# tinyha_hat.net
KiCad netlist of a schematic drawn in EAGLE
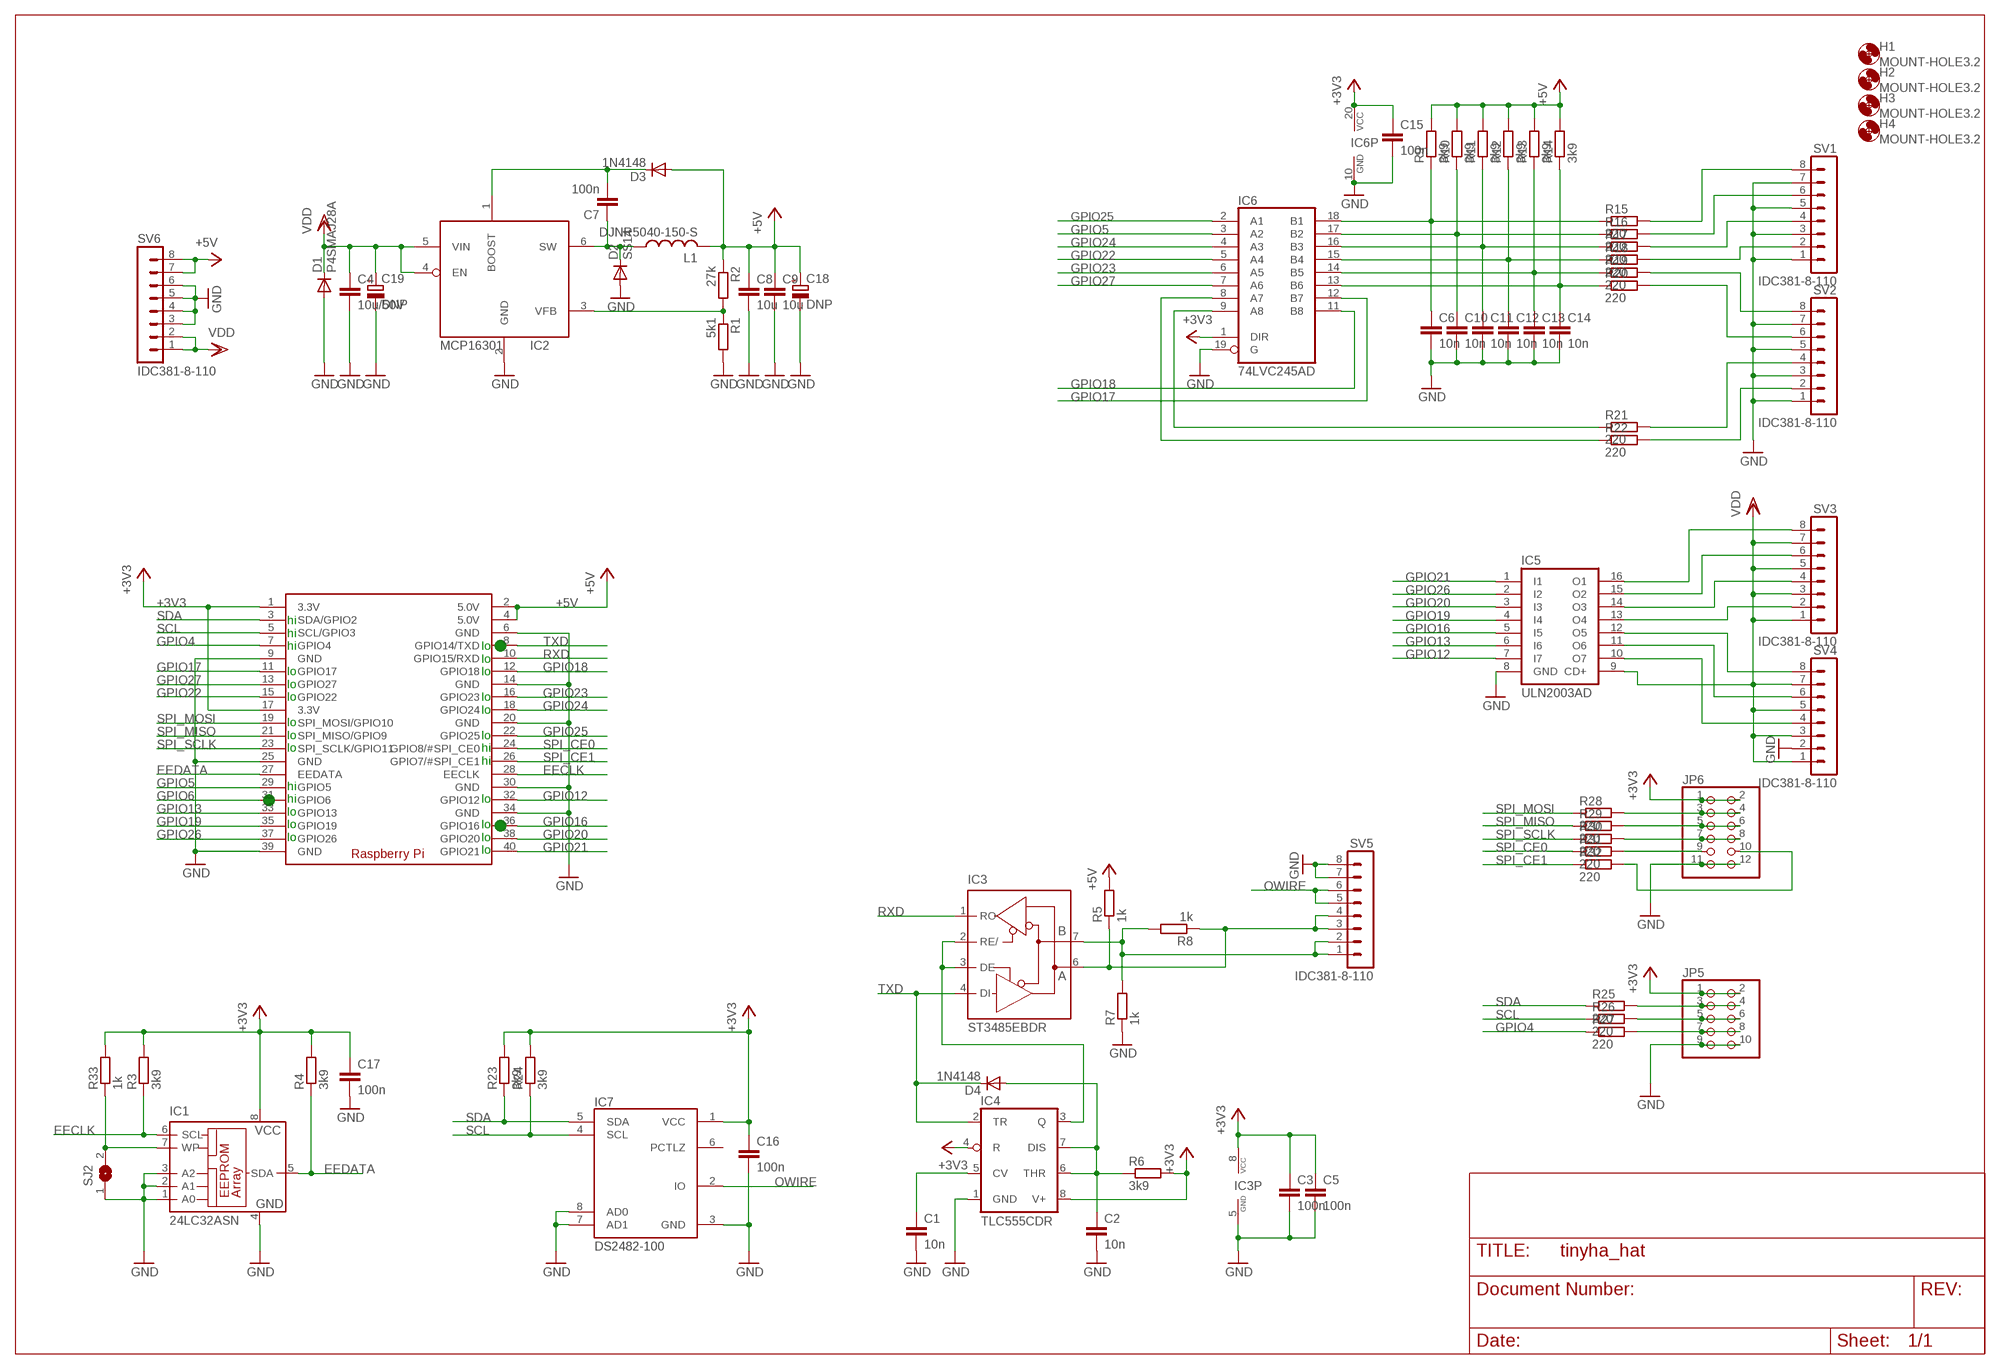
[diagram p0: schematic, sheet 1]

(export (version "E")
  (design (tool "Eeschema 10.0.6"))
  (components
    (comp (ref "C1")
      (value "10n")
      (footprint "eagle-import:C0603K")
      (libsource (lib "eagle-import") (part "C-EUC0603K"))
    )
    (comp (ref "C2")
      (value "10n")
      (footprint "eagle-import:C0603K")
      (libsource (lib "eagle-import") (part "C-EUC0603K"))
    )
    (comp (ref "C3")
      (value "100n")
      (footprint "eagle-import:C0603K")
      (libsource (lib "eagle-import") (part "C-EUC0603K"))
    )
    (comp (ref "C4")
      (value "10u/50V")
      (footprint "eagle-import:C1210K")
      (libsource (lib "eagle-import") (part "C-EUC1210K"))
    )
    (comp (ref "C5")
      (value "100n")
      (footprint "eagle-import:C0603K")
      (libsource (lib "eagle-import") (part "C-EUC0603K"))
    )
    (comp (ref "C6")
      (value "10n")
      (footprint "eagle-import:C0603K")
      (libsource (lib "eagle-import") (part "C-EUC0603K"))
    )
    (comp (ref "C7")
      (value "100n")
      (footprint "eagle-import:C0603K")
      (libsource (lib "eagle-import") (part "C-EUC0603K"))
    )
    (comp (ref "C8")
      (value "10u")
      (footprint "eagle-import:C0805K")
      (libsource (lib "eagle-import") (part "C-EUC0805K"))
    )
    (comp (ref "C9")
      (value "10u")
      (footprint "eagle-import:C0805K")
      (libsource (lib "eagle-import") (part "C-EUC0805K"))
    )
    (comp (ref "C10")
      (value "10n")
      (footprint "eagle-import:C0603K")
      (libsource (lib "eagle-import") (part "C-EUC0603K"))
    )
    (comp (ref "C11")
      (value "10n")
      (footprint "eagle-import:C0603K")
      (libsource (lib "eagle-import") (part "C-EUC0603K"))
    )
    (comp (ref "C12")
      (value "10n")
      (footprint "eagle-import:C0603K")
      (libsource (lib "eagle-import") (part "C-EUC0603K"))
    )
    (comp (ref "C13")
      (value "10n")
      (footprint "eagle-import:C0603K")
      (libsource (lib "eagle-import") (part "C-EUC0603K"))
    )
    (comp (ref "C14")
      (value "10n")
      (footprint "eagle-import:C0603K")
      (libsource (lib "eagle-import") (part "C-EUC0603K"))
    )
    (comp (ref "C15")
      (value "100n")
      (footprint "eagle-import:C0603K")
      (libsource (lib "eagle-import") (part "C-EUC0603K"))
    )
    (comp (ref "C16")
      (value "100n")
      (footprint "eagle-import:C0603K")
      (libsource (lib "eagle-import") (part "C-EUC0603K"))
    )
    (comp (ref "C17")
      (value "100n")
      (footprint "eagle-import:C0603K")
      (libsource (lib "eagle-import") (part "C-EUC0603K"))
    )
    (comp (ref "C18")
      (value "DNP")
      (footprint "eagle-import:E3,5-8")
      (libsource (lib "eagle-import") (part "CPOL-EUE3.5-8"))
    )
    (comp (ref "C19")
      (value "DNP")
      (footprint "eagle-import:E5-10,5")
      (libsource (lib "eagle-import") (part "CPOL-EUE5-10.5"))
    )
    (comp (ref "D1")
      (value "P4SMAJ28A")
      (footprint "eagle-import:DO214AC")
      (libsource (lib "eagle-import") (part "DIODE-DO214AC"))
    )
    (comp (ref "D2")
      (value "SS14")
      (footprint "eagle-import:DO214AC")
      (libsource (lib "eagle-import") (part "DIODE-DO214AC"))
    )
    (comp (ref "D3")
      (value "1N4148")
      (footprint "eagle-import:MICROMELF-W")
      (libsource (lib "eagle-import") (part "DIODE-MICROMELF-W"))
    )
    (comp (ref "D4")
      (value "1N4148")
      (footprint "eagle-import:MICROMELF-W")
      (libsource (lib "eagle-import") (part "DIODE-MICROMELF-W"))
    )
    (comp (ref "H1")
      (value "MOUNT-HOLE3.2")
      (footprint "eagle-import:3,2")
      (libsource (lib "eagle-import") (part "MOUNT-HOLE3.2"))
    )
    (comp (ref "H2")
      (value "MOUNT-HOLE3.2")
      (footprint "eagle-import:3,2")
      (libsource (lib "eagle-import") (part "MOUNT-HOLE3.2"))
    )
    (comp (ref "H3")
      (value "MOUNT-HOLE3.2")
      (footprint "eagle-import:3,2")
      (libsource (lib "eagle-import") (part "MOUNT-HOLE3.2"))
    )
    (comp (ref "H4")
      (value "MOUNT-HOLE3.2")
      (footprint "eagle-import:3,2")
      (libsource (lib "eagle-import") (part "MOUNT-HOLE3.2"))
    )
    (comp (ref "IC1")
      (value "24LC32ASN")
      (footprint "eagle-import:SO-08")
      (fields (field (name "MF") "MICROCHIP") (field (name "MPN") "24LC32A/SN"))
      (libsource (lib "eagle-import") (part "24SNLC32A"))
    )
    (comp (ref "IC2")
      (value "MCP16301")
      (footprint "eagle-import:SOT23-6L")
      (libsource (lib "eagle-import") (part "MCP16301"))
    )
    (comp (ref "IC3")
      (value "ST3485EBDR")
      (footprint "eagle-import:SO08")
      (fields (field (name "MF") "MAXIM") (field (name "MPN") "MAX481CSA"))
      (libsource (lib "eagle-import") (part "MAX481CSA"))
    )
    (comp (ref "IC4")
      (value "TLC555CDR")
      (footprint "eagle-import:SO08")
      (libsource (lib "eagle-import") (part "555DLM"))
    )
    (comp (ref "IC5")
      (value "ULN2003AD")
      (footprint "eagle-import:SO16")
      (libsource (lib "eagle-import") (part "ULN2003AD"))
    )
    (comp (ref "IC6")
      (value "74LVC245AD")
      (footprint "eagle-import:SO20W")
      (libsource (lib "eagle-import") (part "74245DWHC"))
    )
    (comp (ref "IC7")
      (value "DS2482-100")
      (footprint "eagle-import:SOIC-8")
      (libsource (lib "eagle-import") (part "DS2482-100"))
    )
    (comp (ref "JP5")
      (value "PINHD-2X5")
      (footprint "eagle-import:2X05")
      (libsource (lib "eagle-import") (part "PINHD-2X5"))
    )
    (comp (ref "JP6")
      (value "PINHD-2X6")
      (footprint "eagle-import:2X06")
      (libsource (lib "eagle-import") (part "PINHD-2X6"))
    )
    (comp (ref "L1")
      (value "DJNR5040-150-S")
      (footprint "eagle-import:DJNR5040")
      (libsource (lib "eagle-import") (part "DJNR5040"))
    )
    (comp (ref "R1")
      (value "5k1")
      (footprint "eagle-import:R0603")
      (libsource (lib "eagle-import") (part "R-EU_R0603"))
    )
    (comp (ref "R2")
      (value "27k")
      (footprint "eagle-import:R0603")
      (libsource (lib "eagle-import") (part "R-EU_R0603"))
    )
    (comp (ref "R3")
      (value "3k9")
      (footprint "eagle-import:R0603")
      (libsource (lib "eagle-import") (part "R-EU_R0603"))
    )
    (comp (ref "R4")
      (value "3k9")
      (footprint "eagle-import:R0603")
      (libsource (lib "eagle-import") (part "R-EU_R0603"))
    )
    (comp (ref "R5")
      (value "1k")
      (footprint "eagle-import:R0603")
      (libsource (lib "eagle-import") (part "R-EU_R0603"))
    )
    (comp (ref "R6")
      (value "3k9")
      (footprint "eagle-import:R0603")
      (libsource (lib "eagle-import") (part "R-EU_R0603"))
    )
    (comp (ref "R7")
      (value "1k")
      (footprint "eagle-import:R0603")
      (libsource (lib "eagle-import") (part "R-EU_R0603"))
    )
    (comp (ref "R8")
      (value "1k")
      (footprint "eagle-import:R0603")
      (libsource (lib "eagle-import") (part "R-EU_R0603"))
    )
    (comp (ref "R9")
      (value "3k9")
      (footprint "eagle-import:R0603")
      (libsource (lib "eagle-import") (part "R-EU_R0603"))
    )
    (comp (ref "R10")
      (value "3k9")
      (footprint "eagle-import:R0603")
      (libsource (lib "eagle-import") (part "R-EU_R0603"))
    )
    (comp (ref "R11")
      (value "3k9")
      (footprint "eagle-import:R0603")
      (libsource (lib "eagle-import") (part "R-EU_R0603"))
    )
    (comp (ref "R12")
      (value "3k9")
      (footprint "eagle-import:R0603")
      (libsource (lib "eagle-import") (part "R-EU_R0603"))
    )
    (comp (ref "R13")
      (value "3k9")
      (footprint "eagle-import:R0603")
      (libsource (lib "eagle-import") (part "R-EU_R0603"))
    )
    (comp (ref "R14")
      (value "3k9")
      (footprint "eagle-import:R0603")
      (libsource (lib "eagle-import") (part "R-EU_R0603"))
    )
    (comp (ref "R15")
      (value "220")
      (footprint "eagle-import:R0603")
      (libsource (lib "eagle-import") (part "R-EU_R0603"))
    )
    (comp (ref "R16")
      (value "220")
      (footprint "eagle-import:R0603")
      (libsource (lib "eagle-import") (part "R-EU_R0603"))
    )
    (comp (ref "R17")
      (value "220")
      (footprint "eagle-import:R0603")
      (libsource (lib "eagle-import") (part "R-EU_R0603"))
    )
    (comp (ref "R18")
      (value "220")
      (footprint "eagle-import:R0603")
      (libsource (lib "eagle-import") (part "R-EU_R0603"))
    )
    (comp (ref "R19")
      (value "220")
      (footprint "eagle-import:R0603")
      (libsource (lib "eagle-import") (part "R-EU_R0603"))
    )
    (comp (ref "R20")
      (value "220")
      (footprint "eagle-import:R0603")
      (libsource (lib "eagle-import") (part "R-EU_R0603"))
    )
    (comp (ref "R21")
      (value "220")
      (footprint "eagle-import:R0603")
      (libsource (lib "eagle-import") (part "R-EU_R0603"))
    )
    (comp (ref "R22")
      (value "220")
      (footprint "eagle-import:R0603")
      (libsource (lib "eagle-import") (part "R-EU_R0603"))
    )
    (comp (ref "R23")
      (value "3k9")
      (footprint "eagle-import:R0603")
      (libsource (lib "eagle-import") (part "R-EU_R0603"))
    )
    (comp (ref "R24")
      (value "3k9")
      (footprint "eagle-import:R0603")
      (libsource (lib "eagle-import") (part "R-EU_R0603"))
    )
    (comp (ref "R25")
      (value "220")
      (footprint "eagle-import:R0603")
      (libsource (lib "eagle-import") (part "R-EU_R0603"))
    )
    (comp (ref "R26")
      (value "220")
      (footprint "eagle-import:R0603")
      (libsource (lib "eagle-import") (part "R-EU_R0603"))
    )
    (comp (ref "R27")
      (value "220")
      (footprint "eagle-import:R0603")
      (libsource (lib "eagle-import") (part "R-EU_R0603"))
    )
    (comp (ref "R28")
      (value "220")
      (footprint "eagle-import:R0603")
      (libsource (lib "eagle-import") (part "R-EU_R0603"))
    )
    (comp (ref "R29")
      (value "220")
      (footprint "eagle-import:R0603")
      (libsource (lib "eagle-import") (part "R-EU_R0603"))
    )
    (comp (ref "R30")
      (value "220")
      (footprint "eagle-import:R0603")
      (libsource (lib "eagle-import") (part "R-EU_R0603"))
    )
    (comp (ref "R31")
      (value "220")
      (footprint "eagle-import:R0603")
      (libsource (lib "eagle-import") (part "R-EU_R0603"))
    )
    (comp (ref "R32")
      (value "220")
      (footprint "eagle-import:R0603")
      (libsource (lib "eagle-import") (part "R-EU_R0603"))
    )
    (comp (ref "R33")
      (value "1k")
      (footprint "eagle-import:R0603")
      (libsource (lib "eagle-import") (part "R-EU_R0603"))
    )
    (comp (ref "RPI1")
      (value "RASPBERRYPI_BPLUS_ZERO")
      (footprint "eagle-import:PI_HAT_ZERO")
      (libsource (lib "eagle-import") (part "RASPBERRYPI_BPLUS_ZERO"))
    )
    (comp (ref "SJ2") (value "SJ") (footprint "eagle-import:SJ") (libsource (lib "eagle-import") (part "SJ")))
    (comp (ref "SV1")
      (value "IDC381-8-110")
      (footprint "eagle-import:IDC381-8")
      (libsource (lib "eagle-import") (part "MA08-1-IDC"))
    )
    (comp (ref "SV2")
      (value "IDC381-8-110")
      (footprint "eagle-import:IDC381-8")
      (libsource (lib "eagle-import") (part "MA08-1-IDC"))
    )
    (comp (ref "SV3")
      (value "IDC381-8-110")
      (footprint "eagle-import:IDC381-8")
      (libsource (lib "eagle-import") (part "MA08-1-IDC"))
    )
    (comp (ref "SV4")
      (value "IDC381-8-110")
      (footprint "eagle-import:IDC381-8")
      (libsource (lib "eagle-import") (part "MA08-1-IDC"))
    )
    (comp (ref "SV5")
      (value "IDC381-8-110")
      (footprint "eagle-import:IDC381-8")
      (libsource (lib "eagle-import") (part "MA08-1-IDC"))
    )
    (comp (ref "SV6")
      (value "IDC381-8-110")
      (footprint "eagle-import:IDC381-8")
      (libsource (lib "eagle-import") (part "MA08-1-IDC"))
    )
  )
  (nets
    (net (code "1") (name "+3V3") (class "Default")
      (node (ref "C15") (pin "1") (pinfunction "1_1") (pintype "passive"))
      (node (ref "C16") (pin "1") (pinfunction "1_1") (pintype "passive"))
      (node (ref "C17") (pin "1") (pinfunction "1_1") (pintype "passive"))
      (node (ref "C3") (pin "1") (pinfunction "1_1") (pintype "passive"))
      (node (ref "C5") (pin "1") (pinfunction "1_1") (pintype "passive"))
      (node (ref "IC1") (pin "8") (pinfunction "VCC_8") (pintype "power_in"))
      (node (ref "IC3") (pin "8") (pinfunction "VCC_8") (pintype "power_in"))
      (node (ref "IC4") (pin "4") (pinfunction "R_4") (pintype "input"))
      (node (ref "IC4") (pin "8") (pinfunction "V+_8") (pintype "power_in"))
      (node (ref "IC6") (pin "1") (pinfunction "DIR_1") (pintype "input"))
      (node (ref "IC6") (pin "20") (pinfunction "VCC_20") (pintype "power_in"))
      (node (ref "IC7") (pin "1") (pinfunction "VCC_1") (pintype "power_in"))
      (node (ref "JP5") (pin "1") (pinfunction "1_1") (pintype "passive"))
      (node (ref "JP5") (pin "2") (pinfunction "2_2") (pintype "passive"))
      (node (ref "JP6") (pin "1") (pinfunction "1_1") (pintype "passive"))
      (node (ref "JP6") (pin "2") (pinfunction "2_2") (pintype "passive"))
      (node (ref "R23") (pin "2") (pinfunction "2_2") (pintype "passive"))
      (node (ref "R24") (pin "2") (pinfunction "2_2") (pintype "passive"))
      (node (ref "R3") (pin "2") (pinfunction "2_2") (pintype "passive"))
      (node (ref "R33") (pin "2") (pinfunction "2_2") (pintype "passive"))
      (node (ref "R4") (pin "2") (pinfunction "2_2") (pintype "passive"))
      (node (ref "R6") (pin "2") (pinfunction "2_2") (pintype "passive"))
      (node (ref "RPI1") (pin "1") (pinfunction "3.3V_1") (pintype "power_in"))
      (node (ref "RPI1") (pin "17") (pinfunction "3.3V_17") (pintype "power_in"))
    )
    (net (code "2") (name "+5V") (class "Default")
      (node (ref "C18") (pin "+") (pinfunction "+_+") (pintype "passive"))
      (node (ref "C8") (pin "1") (pinfunction "1_1") (pintype "passive"))
      (node (ref "C9") (pin "1") (pinfunction "1_1") (pintype "passive"))
      (node (ref "D3") (pin "A") (pinfunction "A_A") (pintype "passive"))
      (node (ref "L1") (pin "2") (pinfunction "2_2") (pintype "passive"))
      (node (ref "R10") (pin "2") (pinfunction "2_2") (pintype "passive"))
      (node (ref "R11") (pin "2") (pinfunction "2_2") (pintype "passive"))
      (node (ref "R12") (pin "2") (pinfunction "2_2") (pintype "passive"))
      (node (ref "R13") (pin "2") (pinfunction "2_2") (pintype "passive"))
      (node (ref "R14") (pin "2") (pinfunction "2_2") (pintype "passive"))
      (node (ref "R2") (pin "1") (pinfunction "1_1") (pintype "passive"))
      (node (ref "R5") (pin "2") (pinfunction "2_2") (pintype "passive"))
      (node (ref "R9") (pin "2") (pinfunction "2_2") (pintype "passive"))
      (node (ref "RPI1") (pin "2") (pinfunction "5.0V_2") (pintype "power_in"))
      (node (ref "RPI1") (pin "4") (pinfunction "5.0V_4") (pintype "power_in"))
      (node (ref "SV6") (pin "7") (pinfunction "7_7") (pintype "passive"))
      (node (ref "SV6") (pin "8") (pinfunction "8_8") (pintype "passive"))
    )
    (net (code "3") (name "/EECLK") (class "Default")
      (node (ref "IC1") (pin "6") (pinfunction "SCL_6") (pintype "input"))
      (node (ref "R3") (pin "1") (pinfunction "1_1") (pintype "passive"))
      (node (ref "RPI1") (pin "28") (pinfunction "EECLK_28") (pintype "power_in"))
    )
    (net (code "4") (name "/EEDATA") (class "Default")
      (node (ref "IC1") (pin "5") (pinfunction "SDA_5") (pintype "bidirectional"))
      (node (ref "R4") (pin "1") (pinfunction "1_1") (pintype "passive"))
      (node (ref "RPI1") (pin "27") (pinfunction "EEDATA_27") (pintype "bidirectional"))
    )
    (net (code "5") (name "/GPIO4") (class "Default")
      (node (ref "R27") (pin "1") (pinfunction "1_1") (pintype "passive"))
      (node (ref "RPI1") (pin "7") (pinfunction "GPIO4_7") (pintype "bidirectional"))
    )
    (net (code "6") (name "/GPIO5") (class "Default")
      (node (ref "IC6") (pin "3") (pinfunction "A2_3") (pintype "bidirectional"))
      (node (ref "RPI1") (pin "29") (pinfunction "GPIO5_29") (pintype "bidirectional"))
    )
    (net (code "7") (name "/GPIO6") (class "Default")
      (node (ref "RPI1") (pin "31") (pinfunction "GPIO6_31") (pintype "power_in"))
    )
    (net (code "8") (name "/GPIO12") (class "Default")
      (node (ref "IC5") (pin "7") (pinfunction "I7_7") (pintype "input"))
      (node (ref "RPI1") (pin "32") (pinfunction "GPIO12_32") (pintype "bidirectional"))
    )
    (net (code "9") (name "/GPIO13") (class "Default")
      (node (ref "IC5") (pin "6") (pinfunction "I6_6") (pintype "input"))
      (node (ref "RPI1") (pin "33") (pinfunction "GPIO13_33") (pintype "bidirectional"))
    )
    (net (code "10") (name "/GPIO16") (class "Default")
      (node (ref "IC5") (pin "5") (pinfunction "I5_5") (pintype "input"))
      (node (ref "RPI1") (pin "36") (pinfunction "GPIO16_36") (pintype "power_in"))
    )
    (net (code "11") (name "/GPIO17") (class "Default")
      (node (ref "IC6") (pin "12") (pinfunction "B7_12") (pintype "bidirectional"))
      (node (ref "RPI1") (pin "11") (pinfunction "GPIO17_11") (pintype "bidirectional"))
    )
    (net (code "12") (name "/GPIO18") (class "Default")
      (node (ref "IC6") (pin "11") (pinfunction "B8_11") (pintype "bidirectional"))
      (node (ref "RPI1") (pin "12") (pinfunction "GPIO18_12") (pintype "bidirectional"))
    )
    (net (code "13") (name "/GPIO19") (class "Default")
      (node (ref "IC5") (pin "4") (pinfunction "I4_4") (pintype "input"))
      (node (ref "RPI1") (pin "35") (pinfunction "GPIO19_35") (pintype "bidirectional"))
    )
    (net (code "14") (name "/GPIO20") (class "Default")
      (node (ref "IC5") (pin "3") (pinfunction "I3_3") (pintype "input"))
      (node (ref "RPI1") (pin "38") (pinfunction "GPIO20_38") (pintype "bidirectional"))
    )
    (net (code "15") (name "/GPIO21") (class "Default")
      (node (ref "IC5") (pin "1") (pinfunction "I1_1") (pintype "input"))
      (node (ref "RPI1") (pin "40") (pinfunction "GPIO21_40") (pintype "bidirectional"))
    )
    (net (code "16") (name "/GPIO22") (class "Default")
      (node (ref "IC6") (pin "5") (pinfunction "A4_5") (pintype "bidirectional"))
      (node (ref "RPI1") (pin "15") (pinfunction "GPIO22_15") (pintype "bidirectional"))
    )
    (net (code "17") (name "/GPIO23") (class "Default")
      (node (ref "IC6") (pin "6") (pinfunction "A5_6") (pintype "bidirectional"))
      (node (ref "RPI1") (pin "16") (pinfunction "GPIO23_16") (pintype "bidirectional"))
    )
    (net (code "18") (name "/GPIO24") (class "Default")
      (node (ref "IC6") (pin "4") (pinfunction "A3_4") (pintype "bidirectional"))
      (node (ref "RPI1") (pin "18") (pinfunction "GPIO24_18") (pintype "bidirectional"))
    )
    (net (code "19") (name "/GPIO25") (class "Default")
      (node (ref "IC6") (pin "2") (pinfunction "A1_2") (pintype "bidirectional"))
      (node (ref "RPI1") (pin "22") (pinfunction "GPIO25_22") (pintype "bidirectional"))
    )
    (net (code "20") (name "/GPIO26") (class "Default")
      (node (ref "IC5") (pin "2") (pinfunction "I2_2") (pintype "input"))
      (node (ref "RPI1") (pin "37") (pinfunction "GPIO26_37") (pintype "bidirectional"))
    )
    (net (code "21") (name "/GPIO27") (class "Default")
      (node (ref "IC6") (pin "7") (pinfunction "A6_7") (pintype "bidirectional"))
      (node (ref "RPI1") (pin "13") (pinfunction "GPIO27_13") (pintype "bidirectional"))
    )
    (net (code "22") (name "/OWIRE") (class "Default")
      (node (ref "IC7") (pin "2") (pinfunction "IO_2") (pintype "bidirectional"))
      (node (ref "SV5") (pin "5") (pinfunction "5_5") (pintype "passive"))
      (node (ref "SV5") (pin "6") (pinfunction "6_6") (pintype "passive"))
    )
    (net (code "23") (name "/RXD") (class "Default")
      (node (ref "IC3") (pin "1") (pinfunction "RO_1") (pintype "output"))
      (node (ref "RPI1") (pin "10") (pinfunction "GPIO15/RXD_10") (pintype "bidirectional"))
    )
    (net (code "24") (name "/SCL") (class "Default")
      (node (ref "IC7") (pin "4") (pinfunction "SCL_4") (pintype "bidirectional"))
      (node (ref "R24") (pin "1") (pinfunction "1_1") (pintype "passive"))
      (node (ref "R26") (pin "1") (pinfunction "1_1") (pintype "passive"))
      (node (ref "RPI1") (pin "5") (pinfunction "SCL/GPIO3_5") (pintype "bidirectional"))
    )
    (net (code "25") (name "/SDA") (class "Default")
      (node (ref "IC7") (pin "5") (pinfunction "SDA_5") (pintype "bidirectional"))
      (node (ref "R23") (pin "1") (pinfunction "1_1") (pintype "passive"))
      (node (ref "R25") (pin "1") (pinfunction "1_1") (pintype "passive"))
      (node (ref "RPI1") (pin "3") (pinfunction "SDA/GPIO2_3") (pintype "bidirectional"))
    )
    (net (code "26") (name "/SPI_CE0") (class "Default")
      (node (ref "R31") (pin "1") (pinfunction "1_1") (pintype "passive"))
      (node (ref "RPI1") (pin "24") (pinfunction "GPIO8/#SPI_CE0_24") (pintype "bidirectional"))
    )
    (net (code "27") (name "/SPI_CE1") (class "Default")
      (node (ref "R32") (pin "1") (pinfunction "1_1") (pintype "passive"))
      (node (ref "RPI1") (pin "26") (pinfunction "GPIO7/#SPI_CE1_26") (pintype "bidirectional"))
    )
    (net (code "28") (name "/SPI_MISO") (class "Default")
      (node (ref "R29") (pin "1") (pinfunction "1_1") (pintype "passive"))
      (node (ref "RPI1") (pin "21") (pinfunction "SPI_MISO/GPIO9_21") (pintype "bidirectional"))
    )
    (net (code "29") (name "/SPI_MOSI") (class "Default")
      (node (ref "R28") (pin "1") (pinfunction "1_1") (pintype "passive"))
      (node (ref "RPI1") (pin "19") (pinfunction "SPI_MOSI/GPIO10_19") (pintype "bidirectional"))
    )
    (net (code "30") (name "/SPI_SCLK") (class "Default")
      (node (ref "R30") (pin "1") (pinfunction "1_1") (pintype "passive"))
      (node (ref "RPI1") (pin "23") (pinfunction "SPI_SCLK/GPIO11_23") (pintype "bidirectional"))
    )
    (net (code "31") (name "/TXD") (class "Default")
      (node (ref "D4") (pin "C") (pinfunction "C_C") (pintype "passive"))
      (node (ref "IC3") (pin "4") (pinfunction "DI_4") (pintype "input"))
      (node (ref "IC4") (pin "2") (pinfunction "TR_2") (pintype "input"))
      (node (ref "RPI1") (pin "8") (pinfunction "GPIO14/TXD_8") (pintype "output"))
    )
    (net (code "32") (name "GND") (class "Default")
      (node (ref "C1") (pin "2") (pinfunction "2_2") (pintype "passive"))
      (node (ref "C10") (pin "2") (pinfunction "2_2") (pintype "passive"))
      (node (ref "C11") (pin "2") (pinfunction "2_2") (pintype "passive"))
      (node (ref "C12") (pin "2") (pinfunction "2_2") (pintype "passive"))
      (node (ref "C13") (pin "2") (pinfunction "2_2") (pintype "passive"))
      (node (ref "C14") (pin "2") (pinfunction "2_2") (pintype "passive"))
      (node (ref "C15") (pin "2") (pinfunction "2_2") (pintype "passive"))
      (node (ref "C16") (pin "2") (pinfunction "2_2") (pintype "passive"))
      (node (ref "C17") (pin "2") (pinfunction "2_2") (pintype "passive"))
      (node (ref "C18") (pin "-") (pinfunction "-_-") (pintype "passive"))
      (node (ref "C19") (pin "-") (pinfunction "-_-") (pintype "passive"))
      (node (ref "C2") (pin "2") (pinfunction "2_2") (pintype "passive"))
      (node (ref "C3") (pin "2") (pinfunction "2_2") (pintype "passive"))
      (node (ref "C4") (pin "2") (pinfunction "2_2") (pintype "passive"))
      (node (ref "C5") (pin "2") (pinfunction "2_2") (pintype "passive"))
      (node (ref "C6") (pin "2") (pinfunction "2_2") (pintype "passive"))
      (node (ref "C8") (pin "2") (pinfunction "2_2") (pintype "passive"))
      (node (ref "C9") (pin "2") (pinfunction "2_2") (pintype "passive"))
      (node (ref "D1") (pin "A") (pinfunction "A_A") (pintype "passive"))
      (node (ref "D2") (pin "A") (pinfunction "A_A") (pintype "passive"))
      (node (ref "IC1") (pin "1") (pinfunction "A0_1") (pintype "input"))
      (node (ref "IC1") (pin "2") (pinfunction "A1_2") (pintype "input"))
      (node (ref "IC1") (pin "3") (pinfunction "A2_3") (pintype "input"))
      (node (ref "IC1") (pin "4") (pinfunction "GND_4") (pintype "power_in"))
      (node (ref "IC2") (pin "2") (pinfunction "GND_2") (pintype "power_in"))
      (node (ref "IC3") (pin "5") (pinfunction "GND_5") (pintype "power_in"))
      (node (ref "IC4") (pin "1") (pinfunction "GND_1") (pintype "power_in"))
      (node (ref "IC5") (pin "8") (pinfunction "GND_8") (pintype "power_in"))
      (node (ref "IC6") (pin "10") (pinfunction "GND_10") (pintype "power_in"))
      (node (ref "IC6") (pin "19") (pinfunction "G_19") (pintype "input"))
      (node (ref "IC7") (pin "3") (pinfunction "GND_3") (pintype "power_in"))
      (node (ref "IC7") (pin "7") (pinfunction "AD1_7") (pintype "input"))
      (node (ref "IC7") (pin "8") (pinfunction "AD0_8") (pintype "input"))
      (node (ref "JP5") (pin "10") (pinfunction "10_10") (pintype "passive"))
      (node (ref "JP5") (pin "9") (pinfunction "9_9") (pintype "passive"))
      (node (ref "JP6") (pin "11") (pinfunction "11_11") (pintype "passive"))
      (node (ref "JP6") (pin "12") (pinfunction "12_12") (pintype "passive"))
      (node (ref "R1") (pin "2") (pinfunction "2_2") (pintype "passive"))
      (node (ref "R7") (pin "1") (pinfunction "1_1") (pintype "passive"))
      (node (ref "RPI1") (pin "14") (pinfunction "GND_14") (pintype "power_in"))
      (node (ref "RPI1") (pin "20") (pinfunction "GND_20") (pintype "power_in"))
      (node (ref "RPI1") (pin "25") (pinfunction "GND_25") (pintype "power_in"))
      (node (ref "RPI1") (pin "30") (pinfunction "GND_30") (pintype "bidirectional"))
      (node (ref "RPI1") (pin "34") (pinfunction "GND_34") (pintype "bidirectional"))
      (node (ref "RPI1") (pin "39") (pinfunction "GND_39") (pintype "power_in"))
      (node (ref "RPI1") (pin "6") (pinfunction "GND_6") (pintype "power_in"))
      (node (ref "RPI1") (pin "9") (pinfunction "GND_9") (pintype "power_in"))
      (node (ref "SJ2") (pin "1") (pinfunction "1_1") (pintype "passive"))
      (node (ref "SV1") (pin "1") (pinfunction "1_1") (pintype "passive"))
      (node (ref "SV1") (pin "3") (pinfunction "3_3") (pintype "passive"))
      (node (ref "SV1") (pin "5") (pinfunction "5_5") (pintype "passive"))
      (node (ref "SV1") (pin "7") (pinfunction "7_7") (pintype "passive"))
      (node (ref "SV2") (pin "1") (pinfunction "1_1") (pintype "passive"))
      (node (ref "SV2") (pin "3") (pinfunction "3_3") (pintype "passive"))
      (node (ref "SV2") (pin "5") (pinfunction "5_5") (pintype "passive"))
      (node (ref "SV2") (pin "7") (pinfunction "7_7") (pintype "passive"))
      (node (ref "SV4") (pin "2") (pinfunction "2_2") (pintype "passive"))
      (node (ref "SV5") (pin "7") (pinfunction "7_7") (pintype "passive"))
      (node (ref "SV5") (pin "8") (pinfunction "8_8") (pintype "passive"))
      (node (ref "SV6") (pin "3") (pinfunction "3_3") (pintype "passive"))
      (node (ref "SV6") (pin "4") (pinfunction "4_4") (pintype "passive"))
      (node (ref "SV6") (pin "5") (pinfunction "5_5") (pintype "passive"))
      (node (ref "SV6") (pin "6") (pinfunction "6_6") (pintype "passive"))
    )
    (net (code "33") (name "Net-(IC1-WP)") (class "Default")
      (node (ref "IC1") (pin "7") (pinfunction "WP_7") (pintype "input"))
      (node (ref "R33") (pin "1") (pinfunction "1_1") (pintype "passive"))
      (node (ref "SJ2") (pin "2") (pinfunction "2_2") (pintype "passive"))
    )
    (net (code "34") (name "Net-(IC2-BOOST)") (class "Default")
      (node (ref "C7") (pin "2") (pinfunction "2_2") (pintype "passive"))
      (node (ref "D3") (pin "C") (pinfunction "C_C") (pintype "passive"))
      (node (ref "IC2") (pin "1") (pinfunction "BOOST_1") (pintype "passive"))
    )
    (net (code "35") (name "Net-(IC2-SW)") (class "Default")
      (node (ref "C7") (pin "1") (pinfunction "1_1") (pintype "passive"))
      (node (ref "D2") (pin "C") (pinfunction "C_C") (pintype "passive"))
      (node (ref "IC2") (pin "6") (pinfunction "SW_6") (pintype "passive"))
      (node (ref "L1") (pin "1") (pinfunction "1_1") (pintype "passive"))
    )
    (net (code "36") (name "Net-(IC2-VFB)") (class "Default")
      (node (ref "IC2") (pin "3") (pinfunction "VFB_3") (pintype "input"))
      (node (ref "R1") (pin "1") (pinfunction "1_1") (pintype "passive"))
      (node (ref "R2") (pin "2") (pinfunction "2_2") (pintype "passive"))
    )
    (net (code "37") (name "Net-(IC3A-A)") (class "Default")
      (node (ref "IC3") (pin "6") (pinfunction "A_6") (pintype "passive"))
      (node (ref "R5") (pin "1") (pinfunction "1_1") (pintype "passive"))
      (node (ref "R8") (pin "1") (pinfunction "1_1") (pintype "passive"))
      (node (ref "SV5") (pin "3") (pinfunction "3_3") (pintype "passive"))
      (node (ref "SV5") (pin "4") (pinfunction "4_4") (pintype "passive"))
    )
    (net (code "38") (name "Net-(IC3A-B)") (class "Default")
      (node (ref "IC3") (pin "7") (pinfunction "B_7") (pintype "passive"))
      (node (ref "R7") (pin "2") (pinfunction "2_2") (pintype "passive"))
      (node (ref "R8") (pin "2") (pinfunction "2_2") (pintype "passive"))
      (node (ref "SV5") (pin "1") (pinfunction "1_1") (pintype "passive"))
      (node (ref "SV5") (pin "2") (pinfunction "2_2") (pintype "passive"))
    )
    (net (code "39") (name "Net-(IC3A-DE)") (class "Default")
      (node (ref "IC3") (pin "2") (pinfunction "RE/_2") (pintype "input"))
      (node (ref "IC3") (pin "3") (pinfunction "DE_3") (pintype "input"))
      (node (ref "IC4") (pin "3") (pinfunction "Q_3") (pintype "output"))
    )
    (net (code "40") (name "Net-(IC4-CV)") (class "Default")
      (node (ref "C1") (pin "1") (pinfunction "1_1") (pintype "passive"))
      (node (ref "IC4") (pin "5") (pinfunction "CV_5") (pintype "input"))
    )
    (net (code "41") (name "Net-(IC4-DIS)") (class "Default")
      (node (ref "C2") (pin "1") (pinfunction "1_1") (pintype "passive"))
      (node (ref "D4") (pin "A") (pinfunction "A_A") (pintype "passive"))
      (node (ref "IC4") (pin "6") (pinfunction "THR_6") (pintype "input"))
      (node (ref "IC4") (pin "7") (pinfunction "DIS_7") (pintype "input"))
      (node (ref "R6") (pin "1") (pinfunction "1_1") (pintype "passive"))
    )
    (net (code "42") (name "Net-(IC5-O1)") (class "Default")
      (node (ref "IC5") (pin "16") (pinfunction "O1_16") (pintype "open_collector"))
      (node (ref "SV3") (pin "8") (pinfunction "8_8") (pintype "passive"))
    )
    (net (code "43") (name "Net-(IC5-O2)") (class "Default")
      (node (ref "IC5") (pin "15") (pinfunction "O2_15") (pintype "open_collector"))
      (node (ref "SV3") (pin "6") (pinfunction "6_6") (pintype "passive"))
    )
    (net (code "44") (name "Net-(IC5-O3)") (class "Default")
      (node (ref "IC5") (pin "14") (pinfunction "O3_14") (pintype "open_collector"))
      (node (ref "SV3") (pin "4") (pinfunction "4_4") (pintype "passive"))
    )
    (net (code "45") (name "Net-(IC5-O4)") (class "Default")
      (node (ref "IC5") (pin "13") (pinfunction "O4_13") (pintype "open_collector"))
      (node (ref "SV3") (pin "2") (pinfunction "2_2") (pintype "passive"))
    )
    (net (code "46") (name "Net-(IC5-O5)") (class "Default")
      (node (ref "IC5") (pin "12") (pinfunction "O5_12") (pintype "open_collector"))
      (node (ref "SV4") (pin "8") (pinfunction "8_8") (pintype "passive"))
    )
    (net (code "47") (name "Net-(IC5-O6)") (class "Default")
      (node (ref "IC5") (pin "11") (pinfunction "O6_11") (pintype "open_collector"))
      (node (ref "SV4") (pin "6") (pinfunction "6_6") (pintype "passive"))
    )
    (net (code "48") (name "Net-(IC5-O7)") (class "Default")
      (node (ref "IC5") (pin "10") (pinfunction "O7_10") (pintype "open_collector"))
      (node (ref "SV4") (pin "4") (pinfunction "4_4") (pintype "passive"))
    )
    (net (code "49") (name "Net-(IC6A-A7)") (class "Default")
      (node (ref "IC6") (pin "8") (pinfunction "A7_8") (pintype "bidirectional"))
      (node (ref "R22") (pin "1") (pinfunction "1_1") (pintype "passive"))
    )
    (net (code "50") (name "Net-(IC6A-A8)") (class "Default")
      (node (ref "IC6") (pin "9") (pinfunction "A8_9") (pintype "bidirectional"))
      (node (ref "R21") (pin "1") (pinfunction "1_1") (pintype "passive"))
    )
    (net (code "51") (name "Net-(IC6A-B1)") (class "Default")
      (node (ref "C6") (pin "1") (pinfunction "1_1") (pintype "passive"))
      (node (ref "IC6") (pin "18") (pinfunction "B1_18") (pintype "bidirectional"))
      (node (ref "R15") (pin "1") (pinfunction "1_1") (pintype "passive"))
      (node (ref "R9") (pin "1") (pinfunction "1_1") (pintype "passive"))
    )
    (net (code "52") (name "Net-(IC6A-B2)") (class "Default")
      (node (ref "C10") (pin "1") (pinfunction "1_1") (pintype "passive"))
      (node (ref "IC6") (pin "17") (pinfunction "B2_17") (pintype "bidirectional"))
      (node (ref "R10") (pin "1") (pinfunction "1_1") (pintype "passive"))
      (node (ref "R16") (pin "1") (pinfunction "1_1") (pintype "passive"))
    )
    (net (code "53") (name "Net-(IC6A-B3)") (class "Default")
      (node (ref "C11") (pin "1") (pinfunction "1_1") (pintype "passive"))
      (node (ref "IC6") (pin "16") (pinfunction "B3_16") (pintype "bidirectional"))
      (node (ref "R11") (pin "1") (pinfunction "1_1") (pintype "passive"))
      (node (ref "R17") (pin "1") (pinfunction "1_1") (pintype "passive"))
    )
    (net (code "54") (name "Net-(IC6A-B4)") (class "Default")
      (node (ref "C12") (pin "1") (pinfunction "1_1") (pintype "passive"))
      (node (ref "IC6") (pin "15") (pinfunction "B4_15") (pintype "bidirectional"))
      (node (ref "R12") (pin "1") (pinfunction "1_1") (pintype "passive"))
      (node (ref "R18") (pin "1") (pinfunction "1_1") (pintype "passive"))
    )
    (net (code "55") (name "Net-(IC6A-B5)") (class "Default")
      (node (ref "C13") (pin "1") (pinfunction "1_1") (pintype "passive"))
      (node (ref "IC6") (pin "14") (pinfunction "B5_14") (pintype "bidirectional"))
      (node (ref "R13") (pin "1") (pinfunction "1_1") (pintype "passive"))
      (node (ref "R19") (pin "1") (pinfunction "1_1") (pintype "passive"))
    )
    (net (code "56") (name "Net-(IC6A-B6)") (class "Default")
      (node (ref "C14") (pin "1") (pinfunction "1_1") (pintype "passive"))
      (node (ref "IC6") (pin "13") (pinfunction "B6_13") (pintype "bidirectional"))
      (node (ref "R14") (pin "1") (pinfunction "1_1") (pintype "passive"))
      (node (ref "R20") (pin "1") (pinfunction "1_1") (pintype "passive"))
    )
    (net (code "57") (name "Net-(JP5-Pad3)") (class "Default")
      (node (ref "JP5") (pin "3") (pinfunction "3_3") (pintype "passive"))
      (node (ref "JP5") (pin "4") (pinfunction "4_4") (pintype "passive"))
      (node (ref "R25") (pin "2") (pinfunction "2_2") (pintype "passive"))
    )
    (net (code "58") (name "Net-(JP5-Pad5)") (class "Default")
      (node (ref "JP5") (pin "5") (pinfunction "5_5") (pintype "passive"))
      (node (ref "JP5") (pin "6") (pinfunction "6_6") (pintype "passive"))
      (node (ref "R26") (pin "2") (pinfunction "2_2") (pintype "passive"))
    )
    (net (code "59") (name "Net-(JP5-Pad7)") (class "Default")
      (node (ref "JP5") (pin "7") (pinfunction "7_7") (pintype "passive"))
      (node (ref "JP5") (pin "8") (pinfunction "8_8") (pintype "passive"))
      (node (ref "R27") (pin "2") (pinfunction "2_2") (pintype "passive"))
    )
    (net (code "60") (name "Net-(JP6-Pad3)") (class "Default")
      (node (ref "JP6") (pin "3") (pinfunction "3_3") (pintype "passive"))
      (node (ref "JP6") (pin "4") (pinfunction "4_4") (pintype "passive"))
      (node (ref "R28") (pin "2") (pinfunction "2_2") (pintype "passive"))
    )
    (net (code "61") (name "Net-(JP6-Pad5)") (class "Default")
      (node (ref "JP6") (pin "5") (pinfunction "5_5") (pintype "passive"))
      (node (ref "JP6") (pin "6") (pinfunction "6_6") (pintype "passive"))
      (node (ref "R29") (pin "2") (pinfunction "2_2") (pintype "passive"))
    )
    (net (code "62") (name "Net-(JP6-Pad7)") (class "Default")
      (node (ref "JP6") (pin "7") (pinfunction "7_7") (pintype "passive"))
      (node (ref "JP6") (pin "8") (pinfunction "8_8") (pintype "passive"))
      (node (ref "R30") (pin "2") (pinfunction "2_2") (pintype "passive"))
    )
    (net (code "63") (name "Net-(JP6-Pad9)") (class "Default")
      (node (ref "JP6") (pin "9") (pinfunction "9_9") (pintype "passive"))
      (node (ref "R31") (pin "2") (pinfunction "2_2") (pintype "passive"))
    )
    (net (code "64") (name "Net-(JP6-Pad10)") (class "Default")
      (node (ref "JP6") (pin "10") (pinfunction "10_10") (pintype "passive"))
      (node (ref "R32") (pin "2") (pinfunction "2_2") (pintype "passive"))
    )
    (net (code "65") (name "Net-(R15-Pad2)") (class "Default")
      (node (ref "R15") (pin "2") (pinfunction "2_2") (pintype "passive"))
      (node (ref "SV1") (pin "8") (pinfunction "8_8") (pintype "passive"))
    )
    (net (code "66") (name "Net-(R16-Pad2)") (class "Default")
      (node (ref "R16") (pin "2") (pinfunction "2_2") (pintype "passive"))
      (node (ref "SV1") (pin "6") (pinfunction "6_6") (pintype "passive"))
    )
    (net (code "67") (name "Net-(R17-Pad2)") (class "Default")
      (node (ref "R17") (pin "2") (pinfunction "2_2") (pintype "passive"))
      (node (ref "SV1") (pin "4") (pinfunction "4_4") (pintype "passive"))
    )
    (net (code "68") (name "Net-(R18-Pad2)") (class "Default")
      (node (ref "R18") (pin "2") (pinfunction "2_2") (pintype "passive"))
      (node (ref "SV1") (pin "2") (pinfunction "2_2") (pintype "passive"))
    )
    (net (code "69") (name "Net-(R19-Pad2)") (class "Default")
      (node (ref "R19") (pin "2") (pinfunction "2_2") (pintype "passive"))
      (node (ref "SV2") (pin "8") (pinfunction "8_8") (pintype "passive"))
    )
    (net (code "70") (name "Net-(R20-Pad2)") (class "Default")
      (node (ref "R20") (pin "2") (pinfunction "2_2") (pintype "passive"))
      (node (ref "SV2") (pin "6") (pinfunction "6_6") (pintype "passive"))
    )
    (net (code "71") (name "Net-(R21-Pad2)") (class "Default")
      (node (ref "R21") (pin "2") (pinfunction "2_2") (pintype "passive"))
      (node (ref "SV2") (pin "4") (pinfunction "4_4") (pintype "passive"))
    )
    (net (code "72") (name "Net-(R22-Pad2)") (class "Default")
      (node (ref "R22") (pin "2") (pinfunction "2_2") (pintype "passive"))
      (node (ref "SV2") (pin "2") (pinfunction "2_2") (pintype "passive"))
    )
    (net (code "73") (name "VDD") (class "Default")
      (node (ref "C19") (pin "+") (pinfunction "+_+") (pintype "passive"))
      (node (ref "C4") (pin "1") (pinfunction "1_1") (pintype "passive"))
      (node (ref "D1") (pin "C") (pinfunction "C_C") (pintype "passive"))
      (node (ref "IC2") (pin "4") (pinfunction "EN_4") (pintype "input"))
      (node (ref "IC2") (pin "5") (pinfunction "VIN_5") (pintype "power_in"))
      (node (ref "IC5") (pin "9") (pinfunction "CD+_9") (pintype "passive"))
      (node (ref "SV3") (pin "1") (pinfunction "1_1") (pintype "passive"))
      (node (ref "SV3") (pin "3") (pinfunction "3_3") (pintype "passive"))
      (node (ref "SV3") (pin "5") (pinfunction "5_5") (pintype "passive"))
      (node (ref "SV3") (pin "7") (pinfunction "7_7") (pintype "passive"))
      (node (ref "SV4") (pin "1") (pinfunction "1_1") (pintype "passive"))
      (node (ref "SV4") (pin "3") (pinfunction "3_3") (pintype "passive"))
      (node (ref "SV4") (pin "5") (pinfunction "5_5") (pintype "passive"))
      (node (ref "SV4") (pin "7") (pinfunction "7_7") (pintype "passive"))
      (node (ref "SV6") (pin "1") (pinfunction "1_1") (pintype "passive"))
      (node (ref "SV6") (pin "2") (pinfunction "2_2") (pintype "passive"))
    )
    (net (code "74") (name "unconnected-(IC7-PCTLZ-Pad6)") (class "Default")
      (node (ref "IC7") (pin "6") (pinfunction "PCTLZ_6") (pintype "passive"))
    )
  )
)
